# MyProSch4.net
KiCad netlist of a schematic drawn in Altium Designer
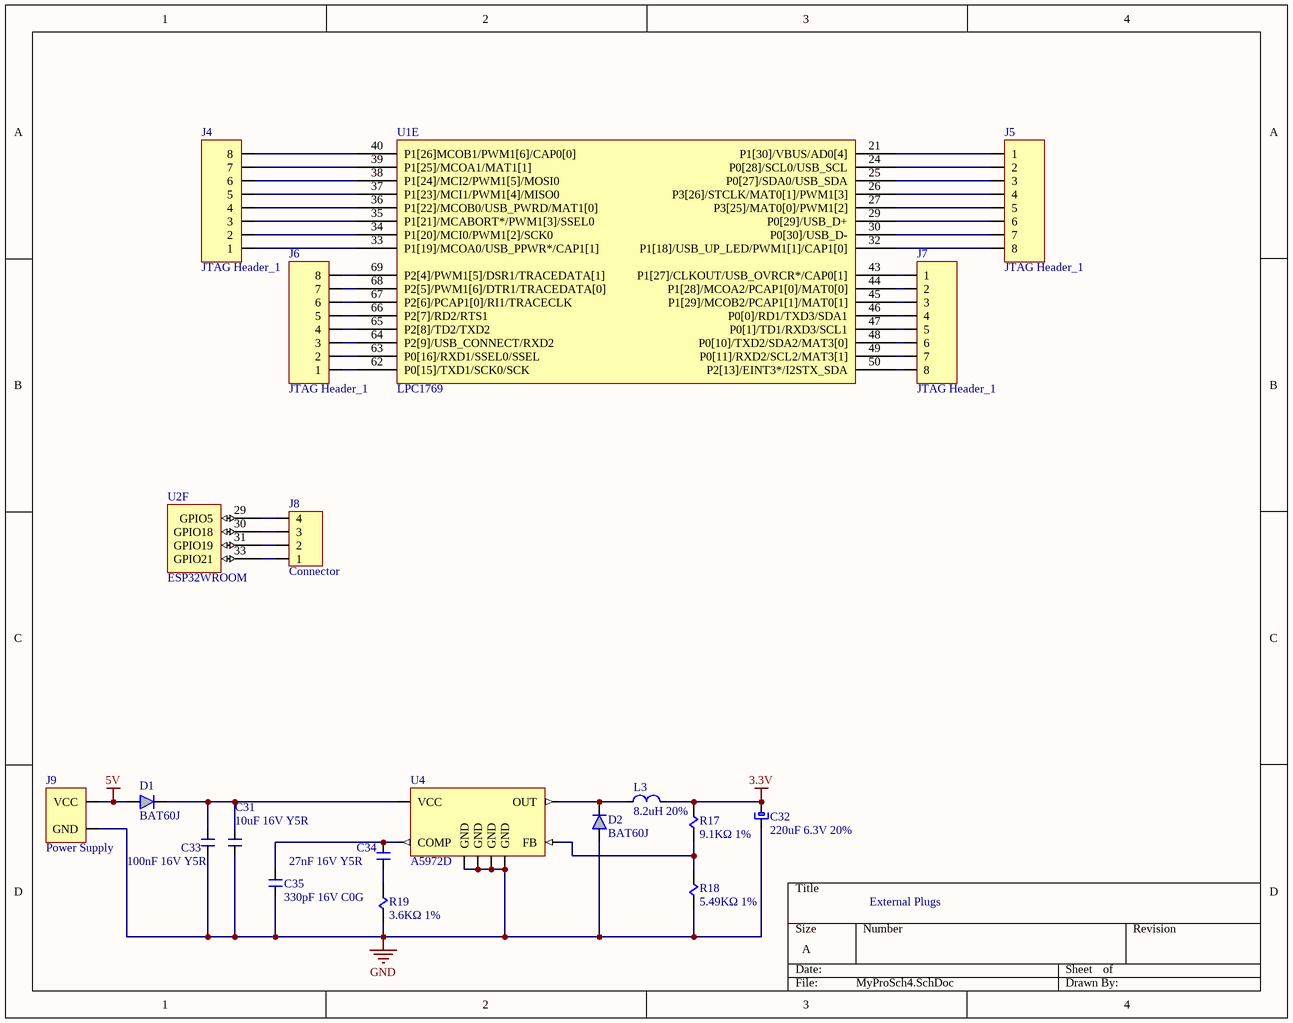
[diagram p0: MyProSch4.SchDoc]

(export (version "E")
  (design (tool "Eeschema 10.0.6"))
  (components
    (comp (ref "C31")
      (value "10uF 16V Y5R")
      (footprint "C_0805")
      (description "Capacitor")
      (libsource (lib "MyPro") (part "Capacitor"))
    )
    (comp (ref "C32")
      (value "220uF 6.3V 20%")
      (footprint "CT_2917_D")
      (libsource (lib "MyPro") (part "Polarized Capacitor"))
    )
    (comp (ref "C33")
      (value "100nF 16V Y5R")
      (footprint "C_0805")
      (description "Capacitor")
      (libsource (lib "MyPro") (part "Capacitor"))
    )
    (comp (ref "C34")
      (value "27nF 16V Y5R")
      (footprint "C_0805")
      (description "Capacitor")
      (libsource (lib "MyPro") (part "Capacitor"))
    )
    (comp (ref "C35")
      (value "330pF 16V C0G")
      (footprint "C_0805")
      (description "Capacitor")
      (libsource (lib "MyPro") (part "Capacitor"))
    )
    (comp (ref "D1")
      (value "BAT60J")
      (footprint "SOD323")
      (description "Generic Diode")
      (libsource (lib "MyPro") (part "Diode"))
    )
    (comp (ref "D2")
      (value "BAT60J")
      (footprint "SOD323")
      (description "Generic Diode")
      (libsource (lib "MyPro") (part "Diode"))
    )
    (comp (ref "J4")
      (value "JTAG Header_1")
      (footprint "HDRM_2.54mm_1X8")
      (libsource (lib "MyPro") (part "Connector1x8"))
    )
    (comp (ref "J5")
      (value "JTAG Header_1")
      (footprint "HDRM_2.54mm_1X8")
      (libsource (lib "") (part "Connector1x8_1"))
    )
    (comp (ref "J6")
      (value "JTAG Header_1")
      (footprint "HDRM_2.54mm_1X8")
      (libsource (lib "MyPro") (part "Connector1x8"))
    )
    (comp (ref "J7")
      (value "JTAG Header_1")
      (footprint "HDRM_2.54mm_1X8")
      (libsource (lib "") (part "Connector1x8_1"))
    )
    (comp (ref "J8")
      (value "Connector")
      (footprint "HDRM_0.1_1X4")
      (libsource (lib "MyPro") (part "Connectorx4"))
    )
    (comp (ref "J9")
      (value "Power Supply")
      (footprint "HDRM_0.1_1x2")
      (libsource (lib "MyPro") (part "Power Connector"))
    )
    (comp (ref "L3")
      (value "8.2uH 20%")
      (footprint "1R5_1710")
      (description "Inductor")
      (libsource (lib "MyPro") (part "Inductor"))
    )
    (comp (ref "R17")
      (value "9.1KΩ 1%")
      (footprint "R_0805")
      (description "Resistor")
      (libsource (lib "MyPro") (part "Resistor"))
    )
    (comp (ref "R18")
      (value "5.49KΩ 1%")
      (footprint "R_0805")
      (description "Resistor")
      (libsource (lib "MyPro") (part "Resistor"))
    )
    (comp (ref "R19")
      (value "3.6KΩ 1%")
      (footprint "R_0805")
      (description "Resistor")
      (libsource (lib "MyPro") (part "Resistor"))
    )
    (comp (ref "U1")
      (value "LPC1769")
      (footprint "LQFP100")
      (description "32 bit ARM Cortex M3")
      (libsource (lib "MyPro") (part "LPC1769"))
    )
    (comp (ref "U2")
      (value "ESP32WROOM")
      (footprint "ESP32_WROOM - duplicate")
      (libsource (lib "MyPro") (part "ESP32WROOM"))
    )
    (comp (ref "U4")
      (value "A5972D")
      (footprint "SO_8")
      (description "Fuente Switching 3.3v 1.5A")
      (libsource (lib "MyPro") (part "A5972D"))
    )
  )
  (nets
    (net (code "1") (name "3.3V") (class "Default")
      (node (ref "C32") (pin "1") (pinfunction "P_1") (pintype "passive"))
      (node (ref "L3") (pin "2") (pinfunction "P2_2") (pintype "passive"))
      (node (ref "R17") (pin "2") (pinfunction "P2_2") (pintype "passive"))
    )
    (net (code "2") (name "5V") (class "Default")
      (node (ref "D1") (pin "1") (pinfunction "A_1") (pintype "passive"))
      (node (ref "J9") (pin "1") (pinfunction "VCC_1") (pintype "passive"))
    )
    (net (code "3") (name "GND") (class "Default")
      (node (ref "C31") (pin "2") (pinfunction "A2_2") (pintype "passive"))
      (node (ref "C32") (pin "2") (pinfunction "N_2") (pintype "passive"))
      (node (ref "C33") (pin "2") (pinfunction "A2_2") (pintype "passive"))
      (node (ref "C35") (pin "2") (pinfunction "A2_2") (pintype "passive"))
      (node (ref "D2") (pin "1") (pinfunction "A_1") (pintype "passive"))
      (node (ref "J9") (pin "2") (pinfunction "GND_2") (pintype "passive"))
      (node (ref "R18") (pin "1") (pinfunction "P1_1") (pintype "passive"))
      (node (ref "R19") (pin "1") (pinfunction "P1_1") (pintype "passive"))
      (node (ref "U4") (pin "2") (pinfunction "GND_2") (pintype "passive"))
      (node (ref "U4") (pin "3") (pinfunction "GND_3") (pintype "passive"))
      (node (ref "U4") (pin "6") (pinfunction "GND_6") (pintype "passive"))
      (node (ref "U4") (pin "7") (pinfunction "GND_7") (pintype "passive"))
    )
    (net (code "4") (name "Net-(C31-A1)") (class "Default")
      (node (ref "C31") (pin "1") (pinfunction "A1_1") (pintype "passive"))
      (node (ref "C33") (pin "1") (pinfunction "A1_1") (pintype "passive"))
      (node (ref "D1") (pin "2") (pinfunction "K_2") (pintype "passive"))
      (node (ref "U4") (pin "8") (pinfunction "VCC_8") (pintype "passive"))
    )
    (net (code "5") (name "Net-(C34-A1)") (class "Default")
      (node (ref "C34") (pin "1") (pinfunction "A1_1") (pintype "passive"))
      (node (ref "C35") (pin "1") (pinfunction "A1_1") (pintype "passive"))
      (node (ref "U4") (pin "4") (pinfunction "COMP_4") (pintype "output"))
    )
    (net (code "6") (name "Net-(C34-A2)") (class "Default")
      (node (ref "C34") (pin "2") (pinfunction "A2_2") (pintype "passive"))
      (node (ref "R19") (pin "2") (pinfunction "P2_2") (pintype "passive"))
    )
    (net (code "7") (name "Net-(D2-K)") (class "Default")
      (node (ref "D2") (pin "2") (pinfunction "K_2") (pintype "passive"))
      (node (ref "L3") (pin "1") (pinfunction "P1_1") (pintype "passive"))
      (node (ref "U4") (pin "1") (pinfunction "OUT_1") (pintype "output"))
    )
    (net (code "8") (name "Net-(R17-P1)") (class "Default")
      (node (ref "R17") (pin "1") (pinfunction "P1_1") (pintype "passive"))
      (node (ref "R18") (pin "2") (pinfunction "P2_2") (pintype "passive"))
      (node (ref "U4") (pin "5") (pinfunction "FB_5") (pintype "input"))
    )
    (net (code "9") (name "Net-(U1E-P0[0]{slash}RD1{slash}TXD3{slash}SDA1)") (class "Default")
      (node (ref "J7") (pin "4") (pinfunction "4_4") (pintype "passive"))
      (node (ref "U1") (pin "46") (pinfunction "P0[0]/RD1/TXD3/SDA1_46") (pintype "passive"))
    )
    (net (code "10") (name "Net-(U1E-P0[1]{slash}TD1{slash}RXD3{slash}SCL1)") (class "Default")
      (node (ref "J7") (pin "5") (pinfunction "5_5") (pintype "passive"))
      (node (ref "U1") (pin "47") (pinfunction "P0[1]/TD1/RXD3/SCL1_47") (pintype "passive"))
    )
    (net (code "11") (name "Net-(U1E-P0[10]{slash}TXD2{slash}SDA2{slash}MAT3[0])") (class "Default")
      (node (ref "J7") (pin "6") (pinfunction "6_6") (pintype "passive"))
      (node (ref "U1") (pin "48") (pinfunction "P0[10]/TXD2/SDA2/MAT3[0]_48") (pintype "passive"))
    )
    (net (code "12") (name "Net-(U1E-P0[11]{slash}RXD2{slash}SCL2{slash}MAT3[1])") (class "Default")
      (node (ref "J7") (pin "7") (pinfunction "7_7") (pintype "passive"))
      (node (ref "U1") (pin "49") (pinfunction "P0[11]/RXD2/SCL2/MAT3[1]_49") (pintype "passive"))
    )
    (net (code "13") (name "Net-(U1E-P0[15]{slash}TXD1{slash}SCK0{slash}SCK)") (class "Default")
      (node (ref "J6") (pin "1") (pinfunction "1_1") (pintype "passive"))
      (node (ref "U1") (pin "62") (pinfunction "P0[15]/TXD1/SCK0/SCK_62") (pintype "passive"))
    )
    (net (code "14") (name "Net-(U1E-P0[16]{slash}RXD1{slash}SSEL0{slash}SSEL)") (class "Default")
      (node (ref "J6") (pin "2") (pinfunction "2_2") (pintype "passive"))
      (node (ref "U1") (pin "63") (pinfunction "P0[16]/RXD1/SSEL0/SSEL_63") (pintype "passive"))
    )
    (net (code "15") (name "Net-(U1E-P0[27]{slash}SDA0{slash}USB_SDA)") (class "Default")
      (node (ref "J5") (pin "3") (pinfunction "3_3") (pintype "passive"))
      (node (ref "U1") (pin "25") (pinfunction "P0[27]/SDA0/USB_SDA_25") (pintype "passive"))
    )
    (net (code "16") (name "Net-(U1E-P0[28]{slash}SCL0{slash}USB_SCL)") (class "Default")
      (node (ref "J5") (pin "2") (pinfunction "2_2") (pintype "passive"))
      (node (ref "U1") (pin "24") (pinfunction "P0[28]/SCL0/USB_SCL_24") (pintype "passive"))
    )
    (net (code "17") (name "Net-(U1E-P0[29]{slash}USB_D+)") (class "Default")
      (node (ref "J5") (pin "6") (pinfunction "6_6") (pintype "passive"))
      (node (ref "U1") (pin "29") (pinfunction "P0[29]/USB_D+_29") (pintype "passive"))
    )
    (net (code "18") (name "Net-(U1E-P0[30]{slash}USB_D-)") (class "Default")
      (node (ref "J5") (pin "7") (pinfunction "7_7") (pintype "passive"))
      (node (ref "U1") (pin "30") (pinfunction "P0[30]/USB_D-_30") (pintype "passive"))
    )
    (net (code "19") (name "Net-(U1E-P1[18]{slash}USB_UP_LED{slash}PWM1[1]{slash}CAP1[0])") (class "Default")
      (node (ref "J5") (pin "8") (pinfunction "8_8") (pintype "passive"))
      (node (ref "U1") (pin "32") (pinfunction "P1[18]/USB_UP_LED/PWM1[1]/CAP1[0]_32") (pintype "passive"))
    )
    (net (code "20") (name "Net-(U1E-P1[19]{slash}MCOA0{slash}USB_PPWR*{slash}CAP1[1])") (class "Default")
      (node (ref "J4") (pin "1") (pinfunction "1_1") (pintype "passive"))
      (node (ref "U1") (pin "33") (pinfunction "P1[19]/MCOA0/USB_PPWR*/CAP1[1]_33") (pintype "passive"))
    )
    (net (code "21") (name "Net-(U1E-P1[20]{slash}MCI0{slash}PWM1[2]{slash}SCK0)") (class "Default")
      (node (ref "J4") (pin "2") (pinfunction "2_2") (pintype "passive"))
      (node (ref "U1") (pin "34") (pinfunction "P1[20]/MCI0/PWM1[2]/SCK0_34") (pintype "passive"))
    )
    (net (code "22") (name "Net-(U1E-P1[21]{slash}MCABORT*{slash}PWM1[3]{slash}SSEL0)") (class "Default")
      (node (ref "J4") (pin "3") (pinfunction "3_3") (pintype "passive"))
      (node (ref "U1") (pin "35") (pinfunction "P1[21]/MCABORT*/PWM1[3]/SSEL0_35") (pintype "passive"))
    )
    (net (code "23") (name "Net-(U1E-P1[22]{slash}MCOB0{slash}USB_PWRD{slash}MAT1[0])") (class "Default")
      (node (ref "J4") (pin "4") (pinfunction "4_4") (pintype "passive"))
      (node (ref "U1") (pin "36") (pinfunction "P1[22]/MCOB0/USB_PWRD/MAT1[0]_36") (pintype "passive"))
    )
    (net (code "24") (name "Net-(U1E-P1[23]{slash}MCI1{slash}PWM1[4]{slash}MISO0)") (class "Default")
      (node (ref "J4") (pin "5") (pinfunction "5_5") (pintype "passive"))
      (node (ref "U1") (pin "37") (pinfunction "P1[23]/MCI1/PWM1[4]/MISO0_37") (pintype "passive"))
    )
    (net (code "25") (name "Net-(U1E-P1[24]{slash}MCI2{slash}PWM1[5]{slash}MOSI0)") (class "Default")
      (node (ref "J4") (pin "6") (pinfunction "6_6") (pintype "passive"))
      (node (ref "U1") (pin "38") (pinfunction "P1[24]/MCI2/PWM1[5]/MOSI0_38") (pintype "passive"))
    )
    (net (code "26") (name "Net-(U1E-P1[25]{slash}MCOA1{slash}MAT1[1])") (class "Default")
      (node (ref "J4") (pin "7") (pinfunction "7_7") (pintype "passive"))
      (node (ref "U1") (pin "39") (pinfunction "P1[25]/MCOA1/MAT1[1]_39") (pintype "passive"))
    )
    (net (code "27") (name "Net-(U1E-P1[26]MCOB1{slash}PWM1[6]{slash}CAP0[0])") (class "Default")
      (node (ref "J4") (pin "8") (pinfunction "8_8") (pintype "passive"))
      (node (ref "U1") (pin "40") (pinfunction "P1[26]MCOB1/PWM1[6]/CAP0[0]_40") (pintype "passive"))
    )
    (net (code "28") (name "Net-(U1E-P1[27]{slash}CLKOUT{slash}USB_OVRCR*{slash}CAP0[1])") (class "Default")
      (node (ref "J7") (pin "1") (pinfunction "1_1") (pintype "passive"))
      (node (ref "U1") (pin "43") (pinfunction "P1[27]/CLKOUT/USB_OVRCR*/CAP0[1]_43") (pintype "passive"))
    )
    (net (code "29") (name "Net-(U1E-P1[28]{slash}MCOA2{slash}PCAP1[0]{slash}MAT0[0])") (class "Default")
      (node (ref "J7") (pin "2") (pinfunction "2_2") (pintype "passive"))
      (node (ref "U1") (pin "44") (pinfunction "P1[28]/MCOA2/PCAP1[0]/MAT0[0]_44") (pintype "passive"))
    )
    (net (code "30") (name "Net-(U1E-P1[29]{slash}MCOB2{slash}PCAP1[1]{slash}MAT0[1])") (class "Default")
      (node (ref "J7") (pin "3") (pinfunction "3_3") (pintype "passive"))
      (node (ref "U1") (pin "45") (pinfunction "P1[29]/MCOB2/PCAP1[1]/MAT0[1]_45") (pintype "passive"))
    )
    (net (code "31") (name "Net-(U1E-P1[30]{slash}VBUS{slash}AD0[4])") (class "Default")
      (node (ref "J5") (pin "1") (pinfunction "1_1") (pintype "passive"))
      (node (ref "U1") (pin "21") (pinfunction "P1[30]/VBUS/AD0[4]_21") (pintype "passive"))
    )
    (net (code "32") (name "Net-(U1E-P2[4]{slash}PWM1[5]{slash}DSR1{slash}TRACEDATA[1])") (class "Default")
      (node (ref "J6") (pin "8") (pinfunction "8_8") (pintype "passive"))
      (node (ref "U1") (pin "69") (pinfunction "P2[4]/PWM1[5]/DSR1/TRACEDATA[1]_69") (pintype "passive"))
    )
    (net (code "33") (name "Net-(U1E-P2[5]{slash}PWM1[6]{slash}DTR1{slash}TRACEDATA[0])") (class "Default")
      (node (ref "J6") (pin "7") (pinfunction "7_7") (pintype "passive"))
      (node (ref "U1") (pin "68") (pinfunction "P2[5]/PWM1[6]/DTR1/TRACEDATA[0]_68") (pintype "passive"))
    )
    (net (code "34") (name "Net-(U1E-P2[6]{slash}PCAP1[0]{slash}RI1{slash}TRACECLK)") (class "Default")
      (node (ref "J6") (pin "6") (pinfunction "6_6") (pintype "passive"))
      (node (ref "U1") (pin "67") (pinfunction "P2[6]/PCAP1[0]/RI1/TRACECLK_67") (pintype "passive"))
    )
    (net (code "35") (name "Net-(U1E-P2[7]{slash}RD2{slash}RTS1)") (class "Default")
      (node (ref "J6") (pin "5") (pinfunction "5_5") (pintype "passive"))
      (node (ref "U1") (pin "66") (pinfunction "P2[7]/RD2/RTS1_66") (pintype "passive"))
    )
    (net (code "36") (name "Net-(U1E-P2[8]{slash}TD2{slash}TXD2)") (class "Default")
      (node (ref "J6") (pin "4") (pinfunction "4_4") (pintype "passive"))
      (node (ref "U1") (pin "65") (pinfunction "P2[8]/TD2/TXD2_65") (pintype "passive"))
    )
    (net (code "37") (name "Net-(U1E-P2[9]{slash}USB_CONNECT{slash}RXD2)") (class "Default")
      (node (ref "J6") (pin "3") (pinfunction "3_3") (pintype "passive"))
      (node (ref "U1") (pin "64") (pinfunction "P2[9]/USB_CONNECT/RXD2_64") (pintype "passive"))
    )
    (net (code "38") (name "Net-(U1E-P2[13]{slash}EINT3*{slash}I2STX_SDA)") (class "Default")
      (node (ref "J7") (pin "8") (pinfunction "8_8") (pintype "passive"))
      (node (ref "U1") (pin "50") (pinfunction "P2[13]/EINT3*/I2STX_SDA_50") (pintype "passive"))
    )
    (net (code "39") (name "Net-(U1E-P3[25]{slash}MAT0[0]{slash}PWM1[2])") (class "Default")
      (node (ref "J5") (pin "5") (pinfunction "5_5") (pintype "passive"))
      (node (ref "U1") (pin "27") (pinfunction "P3[25]/MAT0[0]/PWM1[2]_27") (pintype "passive"))
    )
    (net (code "40") (name "Net-(U1E-P3[26]{slash}STCLK{slash}MAT0[1]{slash}PWM1[3])") (class "Default")
      (node (ref "J5") (pin "4") (pinfunction "4_4") (pintype "passive"))
      (node (ref "U1") (pin "26") (pinfunction "P3[26]/STCLK/MAT0[1]/PWM1[3]_26") (pintype "passive"))
    )
    (net (code "41") (name "Net-(U2F-GPIO5)") (class "Default")
      (node (ref "J8") (pin "4") (pinfunction "4_4") (pintype "passive"))
      (node (ref "U2") (pin "29") (pinfunction "GPIO5_29") (pintype "bidirectional"))
    )
    (net (code "42") (name "Net-(U2F-GPIO18)") (class "Default")
      (node (ref "J8") (pin "3") (pinfunction "3_3") (pintype "passive"))
      (node (ref "U2") (pin "30") (pinfunction "GPIO18_30") (pintype "bidirectional"))
    )
    (net (code "43") (name "Net-(U2F-GPIO19)") (class "Default")
      (node (ref "J8") (pin "2") (pinfunction "2_2") (pintype "passive"))
      (node (ref "U2") (pin "31") (pinfunction "GPIO19_31") (pintype "bidirectional"))
    )
    (net (code "44") (name "Net-(U2F-GPIO21)") (class "Default")
      (node (ref "J8") (pin "1") (pinfunction "1_1") (pintype "passive"))
      (node (ref "U2") (pin "33") (pinfunction "GPIO21_33") (pintype "bidirectional"))
    )
  )
)
